# NMEA0183Breakout-3_0.net
KiCad netlist of a schematic drawn in EAGLE
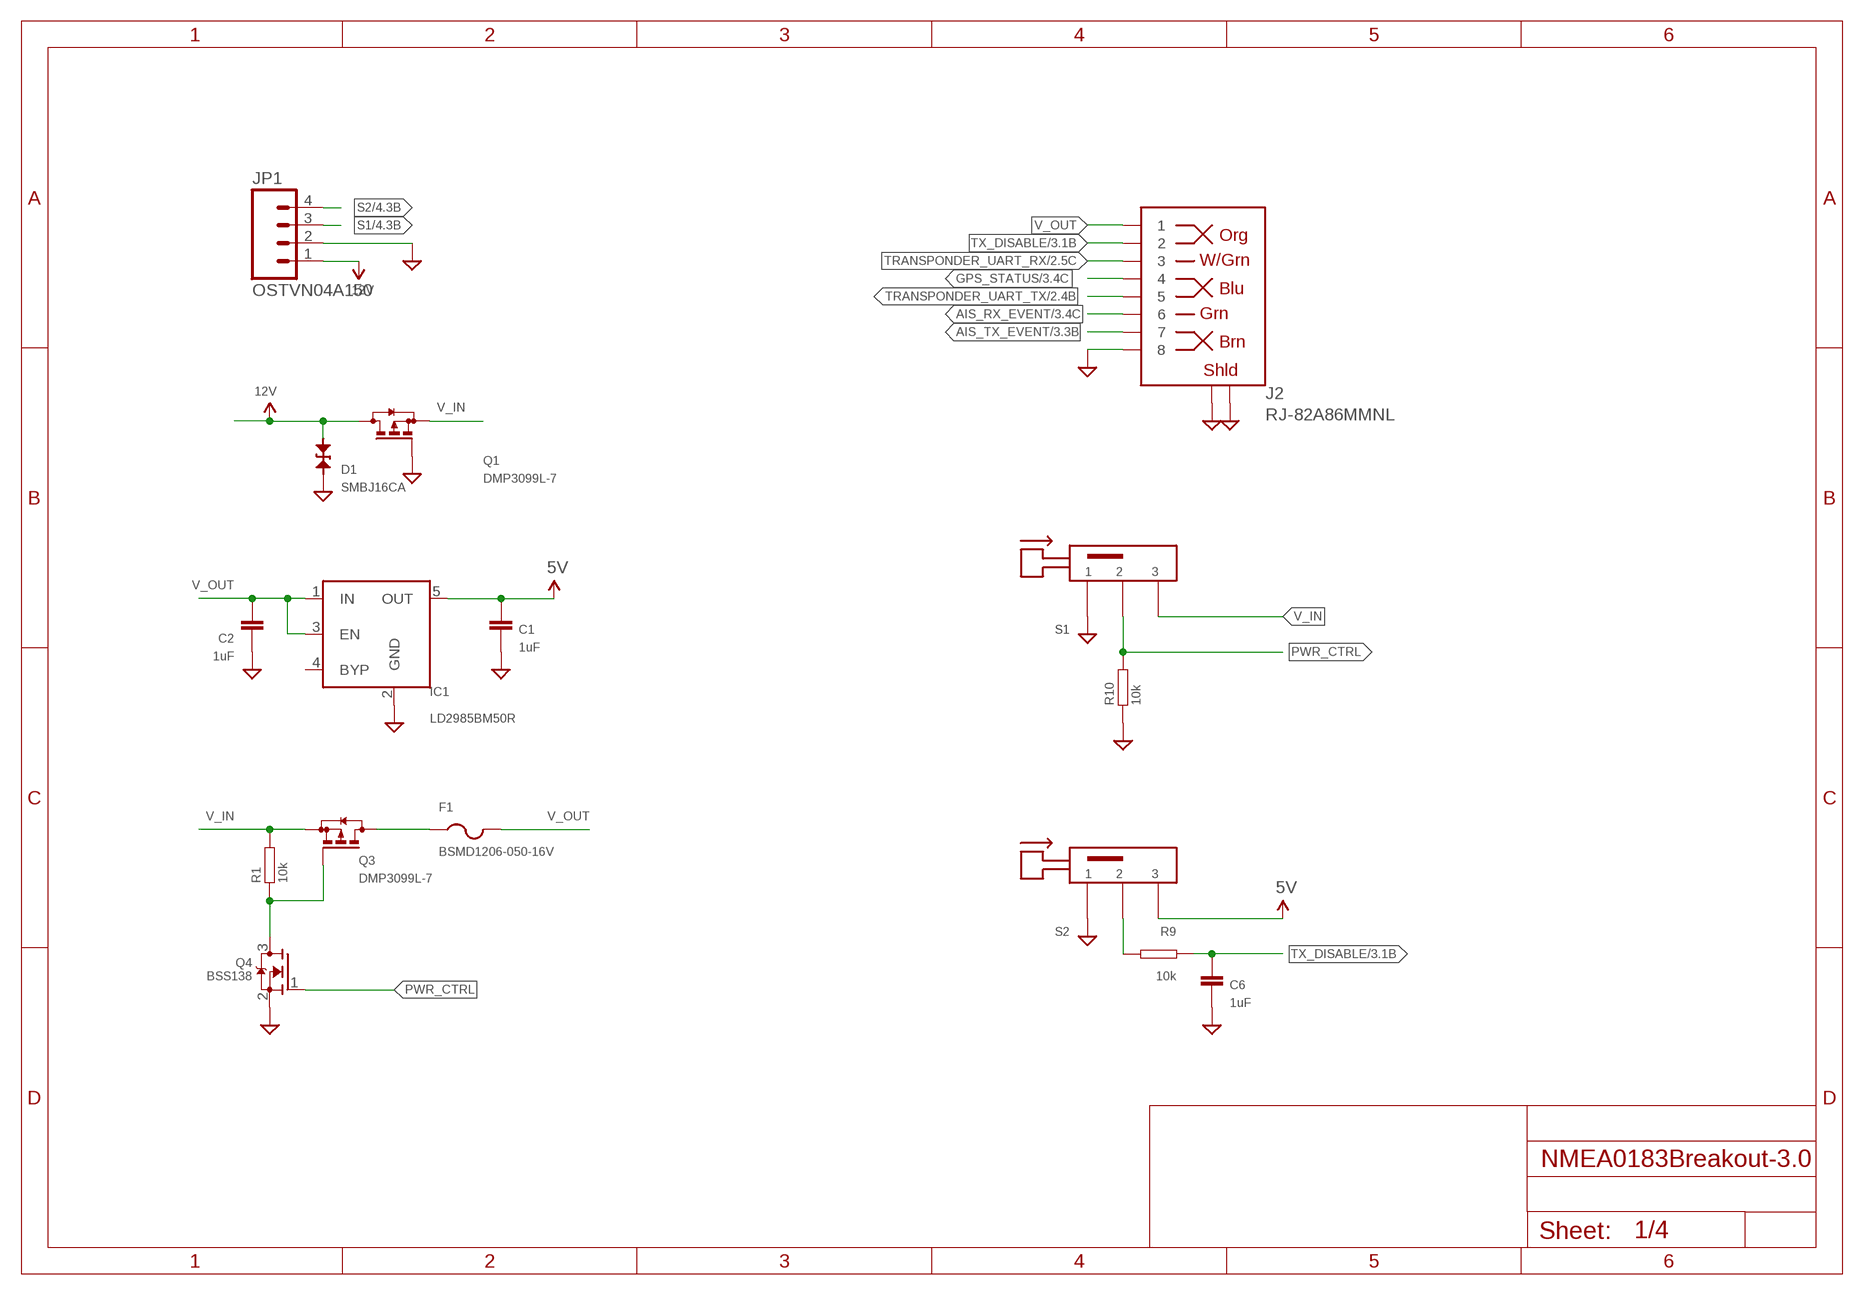
[diagram p0: schematic, sheet 1]
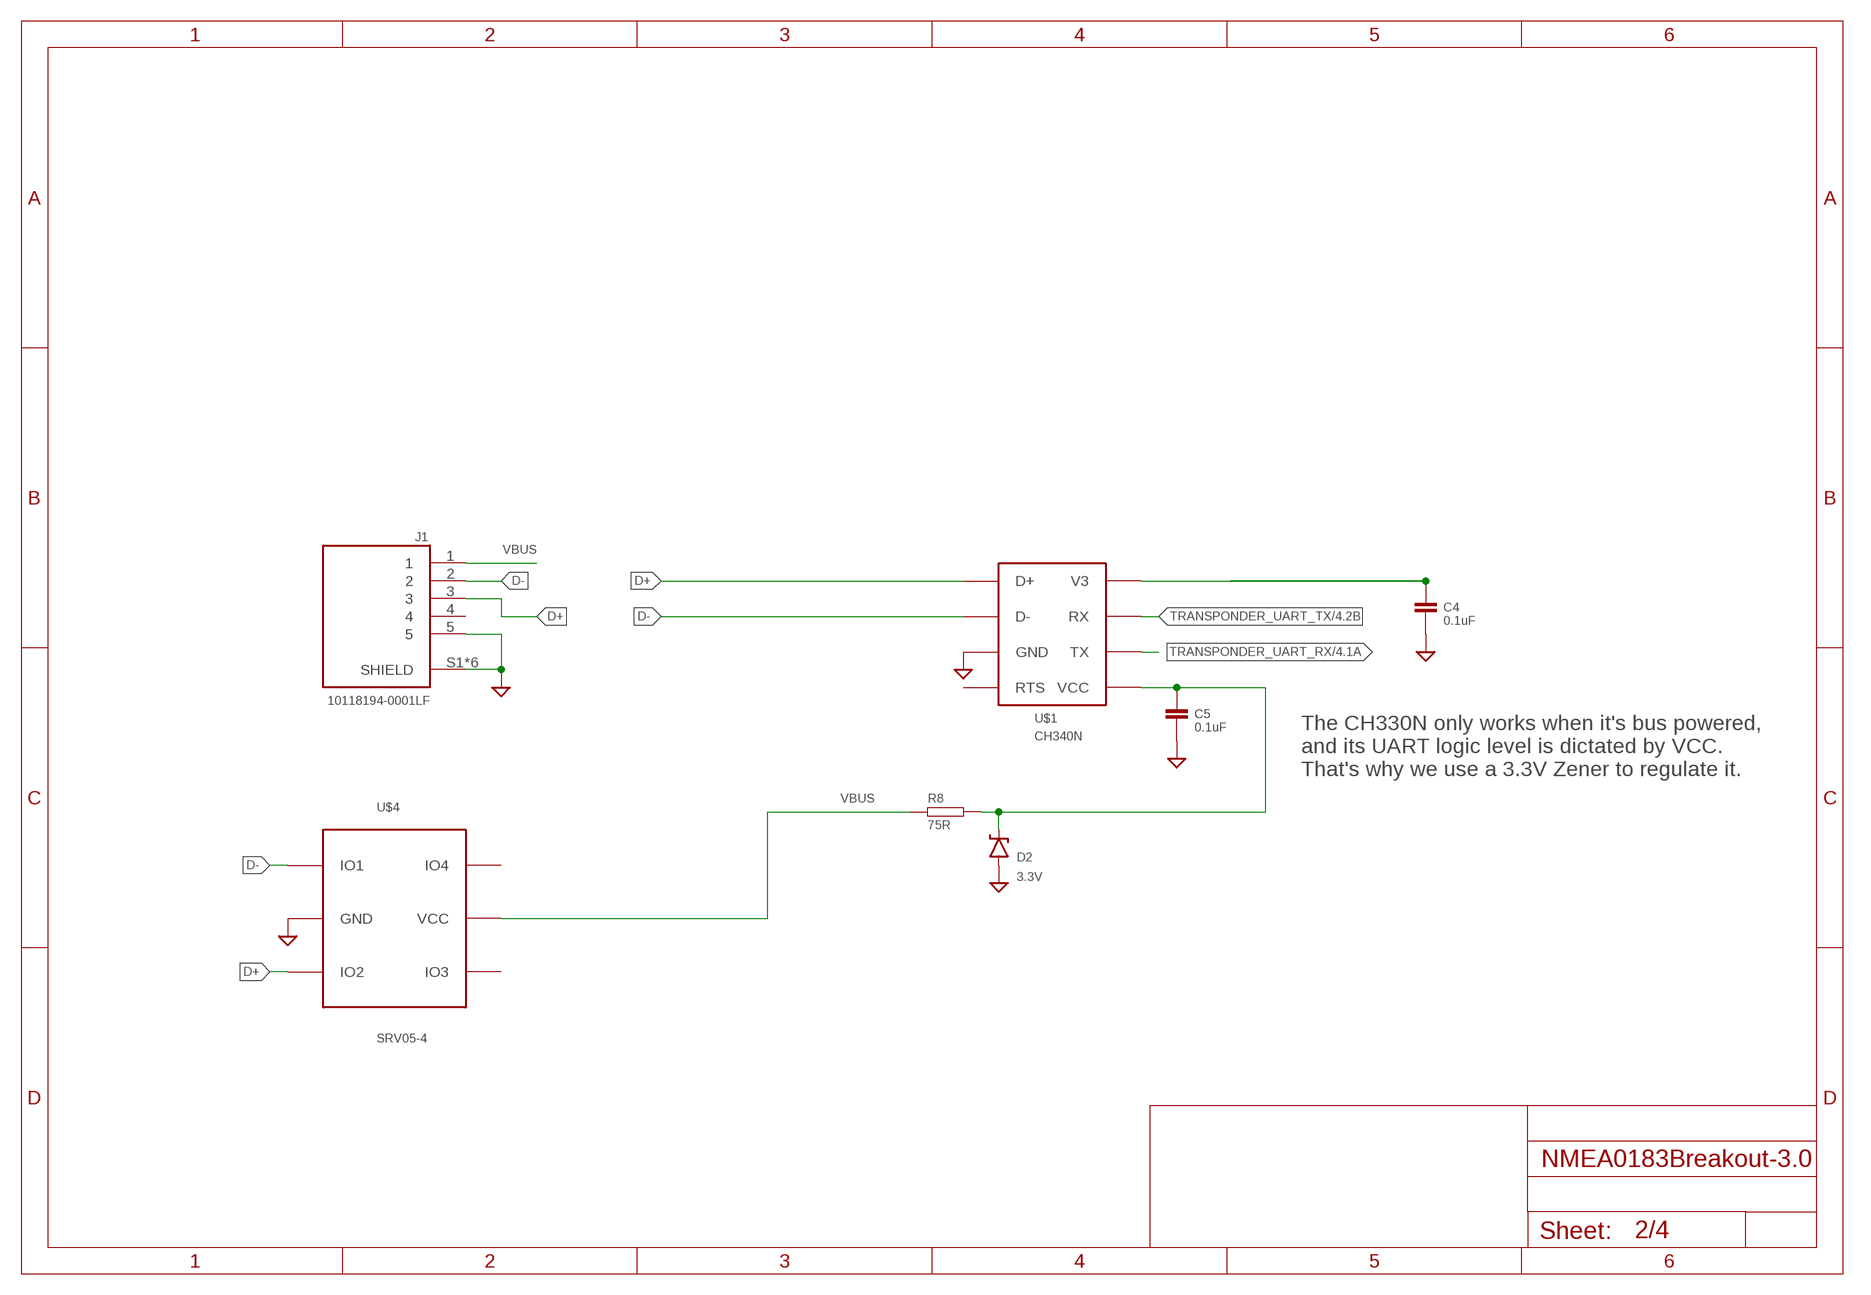
[diagram p1: schematic, sheet 2]
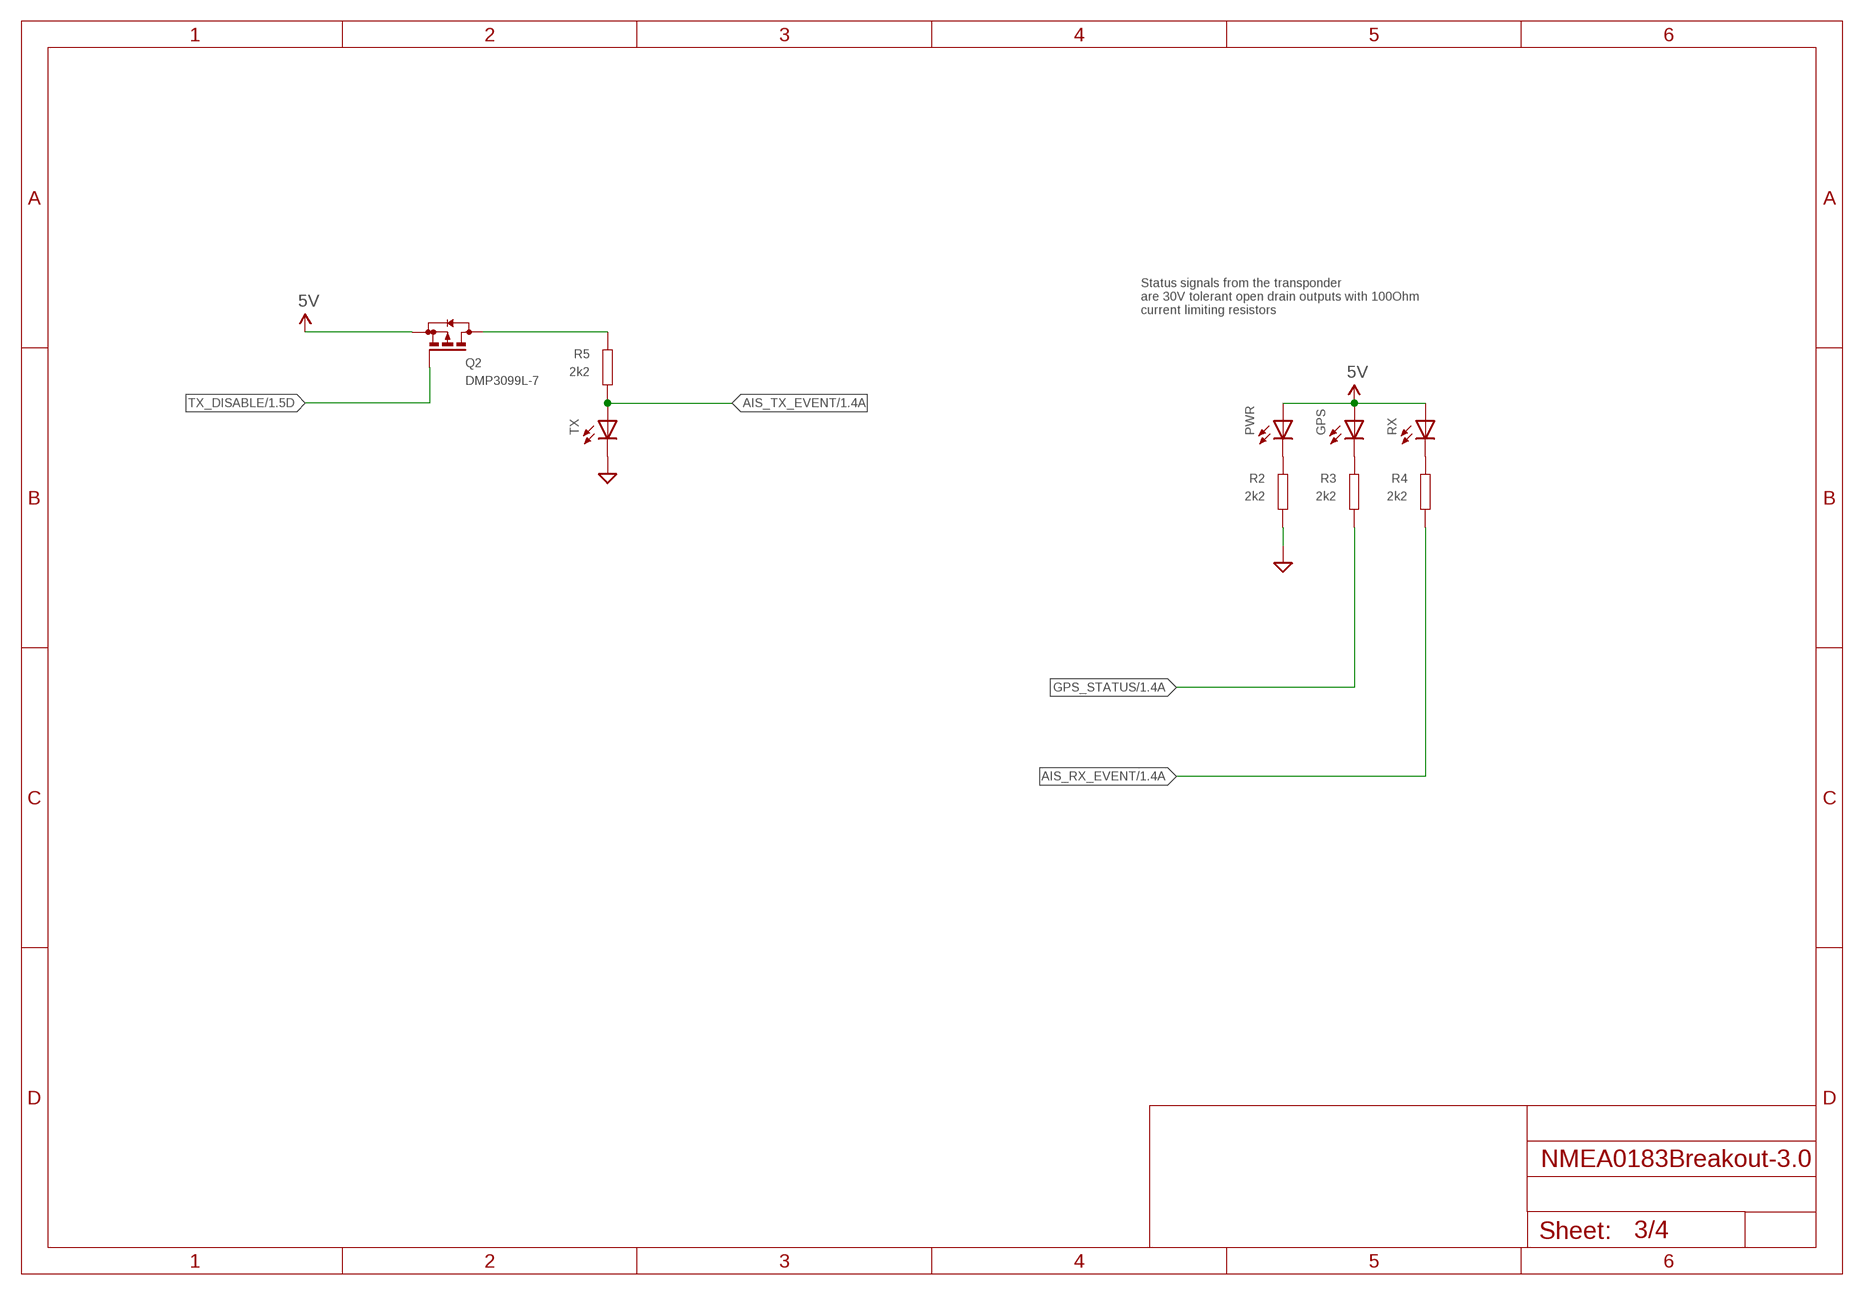
[diagram p2: schematic, sheet 3]
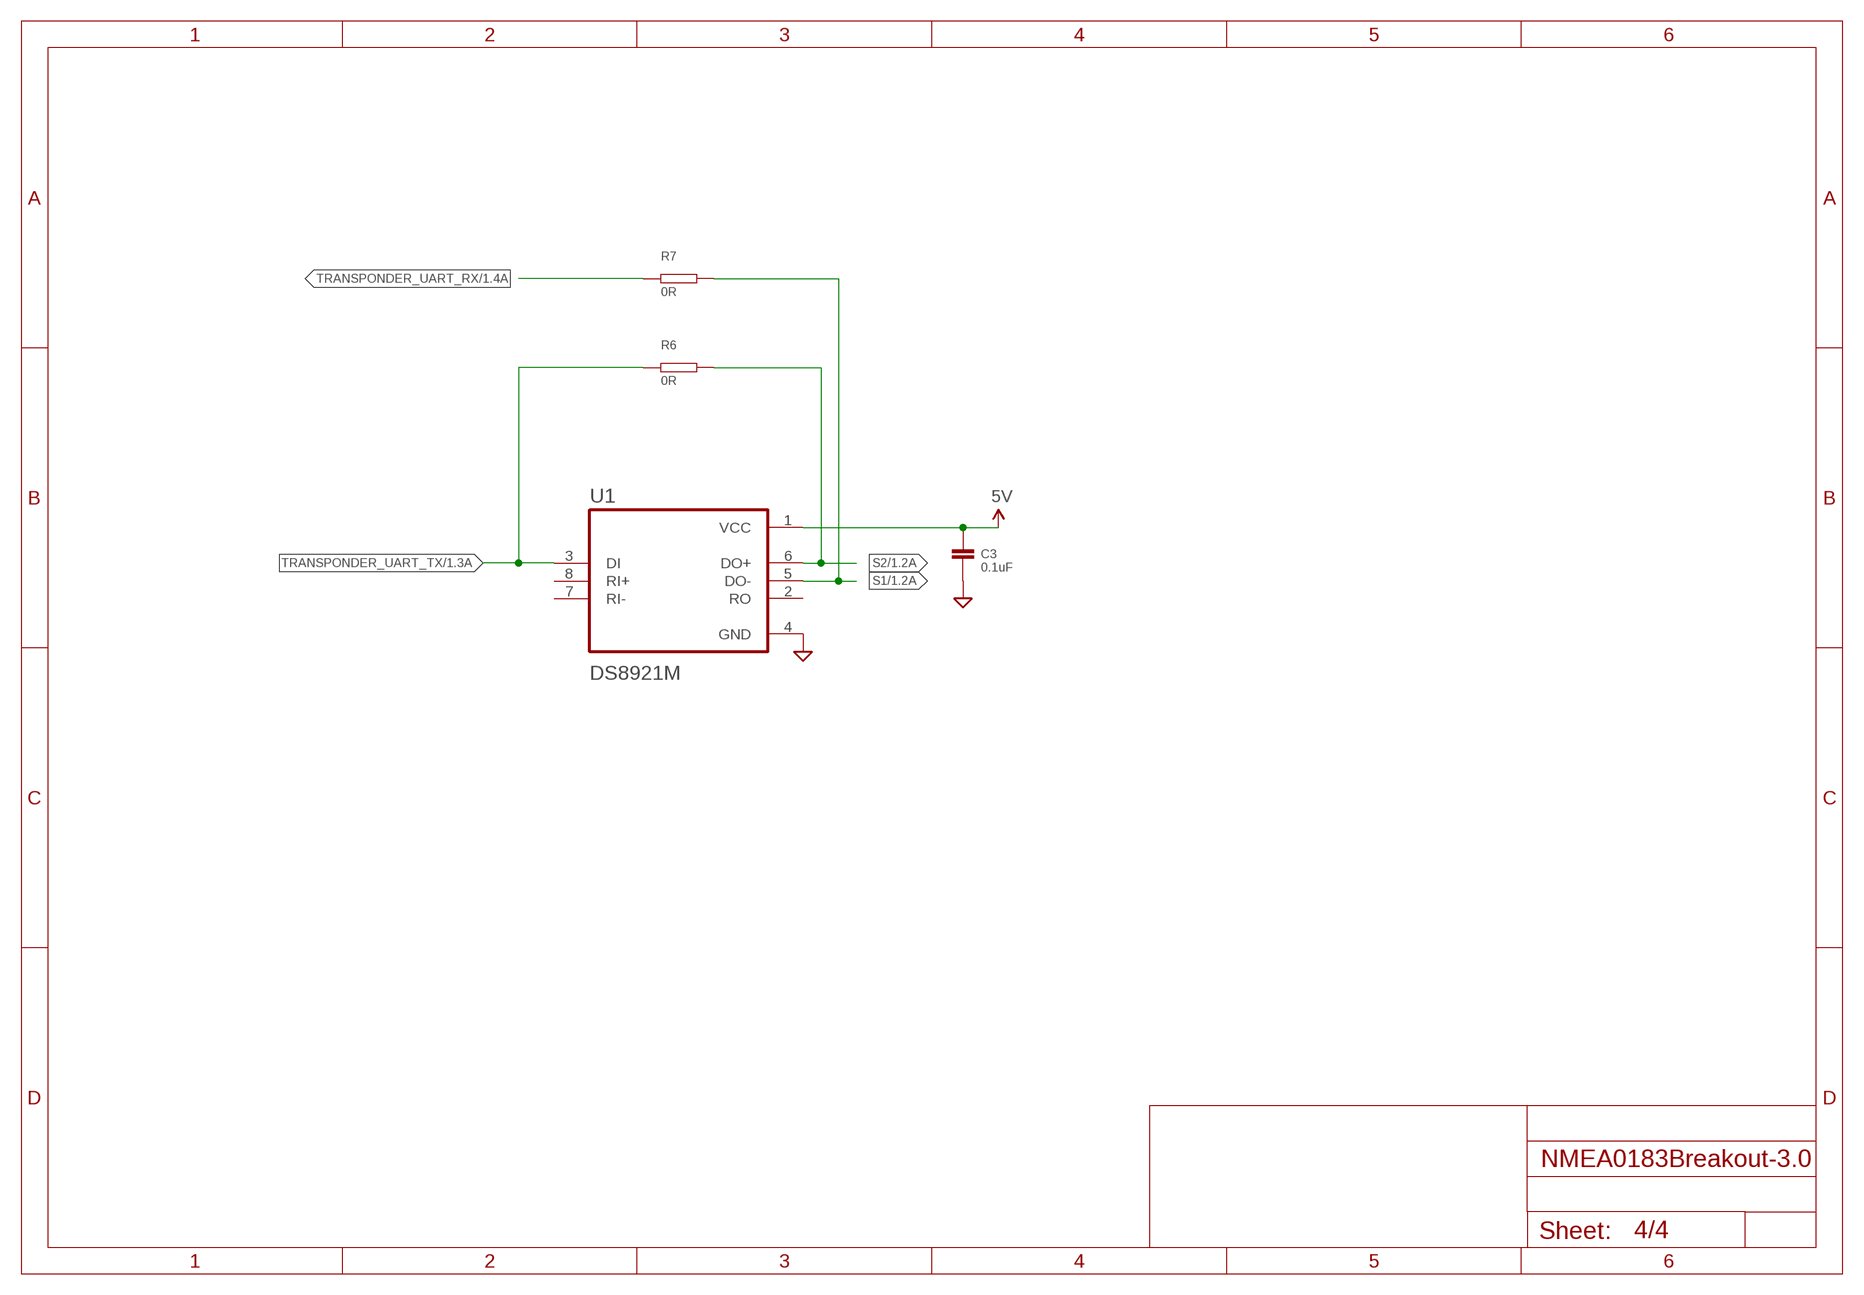
[diagram p3: schematic, sheet 4]

(export (version "E")
  (design (tool "Eeschema 10.0.6"))
  (components
    (comp (ref "C1")
      (value "1uF")
      (footprint "eagle-import:0603")
      (libsource (lib "eagle-import") (part "CAPACITOR0603"))
    )
    (comp (ref "C2")
      (value "1uF")
      (footprint "eagle-import:0603")
      (libsource (lib "eagle-import") (part "CAPACITOR0603"))
    )
    (comp (ref "C6")
      (value "1uF")
      (footprint "eagle-import:0603")
      (libsource (lib "eagle-import") (part "CAPACITOR0603"))
    )
    (comp (ref "D1")
      (value "SMBJ16CA")
      (footprint "eagle-import:SMB-BIDIR")
      (libsource (lib "eagle-import") (part "DIODE-TVS-BIDIRSMB"))
    )
    (comp (ref "F1")
      (value "BSMD1206-050-16V")
      (footprint "eagle-import:R1206")
      (libsource (lib "eagle-import") (part "PTCFUSE-1206"))
    )
    (comp (ref "IC1")
      (value "LD2985BM50R")
      (footprint "eagle-import:SOT23-5")
      (libsource (lib "eagle-import") (part "MIC5219XX"))
    )
    (comp (ref "J2")
      (value "RJ-82A86MMNL")
      (footprint "eagle-import:RJ-82A86MMNL")
      (libsource (lib "eagle-import") (part "RJ-82A86MMNL"))
    )
    (comp (ref "JP1")
      (value "OSTVN04A150")
      (footprint "eagle-import:1X04")
      (libsource (lib "eagle-import") (part "M04PTH"))
    )
    (comp (ref "Q1")
      (value "DMP3099L-7")
      (footprint "eagle-import:SOT23")
      (libsource (lib "eagle-import") (part "BSS84"))
    )
    (comp (ref "Q3")
      (value "DMP3099L-7")
      (footprint "eagle-import:SOT23")
      (libsource (lib "eagle-import") (part "BSS84"))
    )
    (comp (ref "Q4")
      (value "BSS138")
      (footprint "eagle-import:SOT23")
      (libsource (lib "eagle-import") (part "MOSFET-NREFLOW"))
    )
    (comp (ref "R1")
      (value "10k")
      (footprint "eagle-import:0603")
      (libsource (lib "eagle-import") (part "RESISTOR0603"))
    )
    (comp (ref "R9")
      (value "10k")
      (footprint "eagle-import:0603")
      (libsource (lib "eagle-import") (part "RESISTOR0603"))
    )
    (comp (ref "R10")
      (value "10k")
      (footprint "eagle-import:0603")
      (libsource (lib "eagle-import") (part "RESISTOR0603"))
    )
    (comp (ref "S1")
      (value "LC1258XXNP")
      (footprint "eagle-import:LC1258XXNP")
      (libsource (lib "eagle-import") (part "LC1258XXNP"))
    )
    (comp (ref "S2")
      (value "LC1258XXNP")
      (footprint "eagle-import:LC1258XXNP")
      (libsource (lib "eagle-import") (part "LC1258XXNP"))
    )
    (comp (ref "GPS")
      (value "LEDCHIPLED_1206")
      (footprint "eagle-import:CHIPLED_1206")
      (fields (field (name "PARTNO") "TJ-S3216CL9T5ALC2G-A5"))
      (libsource (lib "eagle-import") (part "LEDCHIPLED_1206"))
    )
    (comp (ref "PWR")
      (value "LEDCHIPLED_1206")
      (footprint "eagle-import:CHIPLED_1206")
      (fields (field (name "PARTNO") "TJ-S3216CL9T5ALC2G-A5"))
      (libsource (lib "eagle-import") (part "LEDCHIPLED_1206"))
    )
    (comp (ref "Q2")
      (value "DMP3099L-7")
      (footprint "eagle-import:SOT23")
      (libsource (lib "eagle-import") (part "BSS84"))
    )
    (comp (ref "R2")
      (value "2k2")
      (footprint "eagle-import:0603")
      (libsource (lib "eagle-import") (part "RESISTOR0603"))
    )
    (comp (ref "R3")
      (value "2k2")
      (footprint "eagle-import:0603")
      (libsource (lib "eagle-import") (part "RESISTOR0603"))
    )
    (comp (ref "R4")
      (value "2k2")
      (footprint "eagle-import:0603")
      (libsource (lib "eagle-import") (part "RESISTOR0603"))
    )
    (comp (ref "R5")
      (value "2k2")
      (footprint "eagle-import:0603")
      (libsource (lib "eagle-import") (part "RESISTOR0603"))
    )
    (comp (ref "RX")
      (value "LEDCHIPLED_1206")
      (footprint "eagle-import:CHIPLED_1206")
      (fields (field (name "PARTNO") "TJ-S3216CL9T5ALC2G-A5"))
      (libsource (lib "eagle-import") (part "LEDCHIPLED_1206"))
    )
    (comp (ref "TX")
      (value "LEDCHIPLED_1206")
      (footprint "eagle-import:CHIPLED_1206")
      (fields (field (name "PARTNO") "TJ-S3216CL9T5ALC2G-A5"))
      (libsource (lib "eagle-import") (part "LEDCHIPLED_1206"))
    )
    (comp (ref "C4")
      (value "0.1uF")
      (footprint "eagle-import:0603")
      (libsource (lib "eagle-import") (part "CAPACITOR0603"))
    )
    (comp (ref "C5")
      (value "0.1uF")
      (footprint "eagle-import:0603")
      (libsource (lib "eagle-import") (part "CAPACITOR0603"))
    )
    (comp (ref "D2")
      (value "3.3V")
      (footprint "eagle-import:SOD-323")
      (libsource (lib "eagle-import") (part "DIODE-ZENER3.3V"))
    )
    (comp (ref "J1")
      (value "10118194-0001LF")
      (footprint "eagle-import:AMPHENOL_10118194-0001LF")
      (fields (field (name "MF") "Amphenol ICC (FCI)"))
      (libsource (lib "eagle-import") (part "10118194-0001LF"))
    )
    (comp (ref "R8")
      (value "75R")
      (footprint "eagle-import:0603")
      (libsource (lib "eagle-import") (part "RESISTOR0603"))
    )
    (comp (ref "U$1")
      (value "CH340N")
      (footprint "eagle-import:SOIC-8")
      (libsource (lib "eagle-import") (part "CH330N"))
    )
    (comp (ref "U$4")
      (value "SRV05-4")
      (footprint "eagle-import:SOT23-6")
      (libsource (lib "eagle-import") (part "SRV05-4"))
    )
    (comp (ref "C3")
      (value "0.1uF")
      (footprint "eagle-import:0603")
      (libsource (lib "eagle-import") (part "CAPACITOR0603"))
    )
    (comp (ref "R6")
      (value "0R")
      (footprint "eagle-import:0603")
      (libsource (lib "eagle-import") (part "RESISTOR0603"))
    )
    (comp (ref "R7")
      (value "0R")
      (footprint "eagle-import:0603")
      (libsource (lib "eagle-import") (part "RESISTOR0603"))
    )
    (comp (ref "U1")
      (value "DS8921M")
      (footprint "eagle-import:SOIC127P599X175-8N")
      (fields (field (name "MF") "Texas Instruments") (field (name "MP") "DS8921M/NOPB"))
      (libsource (lib "eagle-import") (part "DS8921M"))
    )
  )
  (nets
    (net (code "1") (name "5V") (class "Default")
      (node (ref "C1") (pin "P$1") (pinfunction "1_P$1") (pintype "passive"))
      (node (ref "C3") (pin "P$1") (pinfunction "1_P$1") (pintype "passive"))
      (node (ref "GPS") (pin "A") (pinfunction "A_A") (pintype "passive"))
      (node (ref "IC1") (pin "5") (pinfunction "OUT_5") (pintype "output"))
      (node (ref "PWR") (pin "A") (pinfunction "A_A") (pintype "passive"))
      (node (ref "Q2") (pin "2") (pinfunction "S_2") (pintype "passive"))
      (node (ref "RX") (pin "A") (pinfunction "A_A") (pintype "passive"))
      (node (ref "S2") (pin "P$3") (pinfunction "3_P$3") (pintype "bidirectional"))
      (node (ref "U1") (pin "1") (pinfunction "VCC_1") (pintype "power_in"))
    )
    (net (code "2") (name "12V") (class "Default")
      (node (ref "D1") (pin "A") (pinfunction "P$1_A") (pintype "bidirectional"))
      (node (ref "JP1") (pin "1") (pinfunction "1_1") (pintype "passive"))
      (node (ref "Q1") (pin "3") (pinfunction "D_3") (pintype "passive"))
    )
    (net (code "3") (name "AIS_RX_EVENT") (class "Default")
      (node (ref "J2") (pin "P$6") (pinfunction "6_P$6") (pintype "bidirectional"))
      (node (ref "R4") (pin "P$2") (pinfunction "P$2_P$2") (pintype "passive"))
    )
    (net (code "4") (name "AIS_TX_EVENT") (class "Default")
      (node (ref "J2") (pin "P$7") (pinfunction "7_P$7") (pintype "bidirectional"))
      (node (ref "R5") (pin "P$2") (pinfunction "P$2_P$2") (pintype "passive"))
      (node (ref "TX") (pin "A") (pinfunction "A_A") (pintype "passive"))
    )
    (net (code "5") (name "D+") (class "Default")
      (node (ref "J1") (pin "3") (pinfunction "3_3") (pintype "passive"))
      (node (ref "U$1") (pin "1") (pinfunction "D+_1") (pintype "bidirectional"))
      (node (ref "U$4") (pin "3") (pinfunction "IO2_3") (pintype "bidirectional"))
    )
    (net (code "6") (name "D-") (class "Default")
      (node (ref "J1") (pin "2") (pinfunction "2_2") (pintype "passive"))
      (node (ref "U$1") (pin "2") (pinfunction "D-_2") (pintype "bidirectional"))
      (node (ref "U$4") (pin "1") (pinfunction "IO1_1") (pintype "bidirectional"))
    )
    (net (code "7") (name "GND") (class "Default")
      (node (ref "C1") (pin "P$2") (pinfunction "2_P$2") (pintype "passive"))
      (node (ref "C2") (pin "P$2") (pinfunction "2_P$2") (pintype "passive"))
      (node (ref "C3") (pin "P$2") (pinfunction "2_P$2") (pintype "passive"))
      (node (ref "C4") (pin "P$2") (pinfunction "2_P$2") (pintype "passive"))
      (node (ref "C5") (pin "P$2") (pinfunction "2_P$2") (pintype "passive"))
      (node (ref "C6") (pin "P$2") (pinfunction "2_P$2") (pintype "passive"))
      (node (ref "D1") (pin "C") (pinfunction "P$2_C") (pintype "bidirectional"))
      (node (ref "D2") (pin "A") (pinfunction "A_A") (pintype "passive"))
      (node (ref "IC1") (pin "2") (pinfunction "GND_2") (pintype "power_in"))
      (node (ref "J1") (pin "5") (pinfunction "5_5") (pintype "passive"))
      (node (ref "J1") (pin "S1") (pinfunction "SHIELD_S1") (pintype "passive"))
      (node (ref "J1") (pin "S2") (pinfunction "SHIELD_S2") (pintype "passive"))
      (node (ref "J1") (pin "S3") (pinfunction "SHIELD_S3") (pintype "passive"))
      (node (ref "J1") (pin "S4") (pinfunction "SHIELD_S4") (pintype "passive"))
      (node (ref "J1") (pin "S5") (pinfunction "SHIELD_S5") (pintype "passive"))
      (node (ref "J1") (pin "S6") (pinfunction "SHIELD_S6") (pintype "passive"))
      (node (ref "J2") (pin "P$10") (pinfunction "SHLD_P$10") (pintype "bidirectional"))
      (node (ref "J2") (pin "P$11") (pinfunction "SHLD_P$11") (pintype "bidirectional"))
      (node (ref "J2") (pin "P$12") (pinfunction "SHLD_P$12") (pintype "bidirectional"))
      (node (ref "J2") (pin "P$8") (pinfunction "8_P$8") (pintype "bidirectional"))
      (node (ref "J2") (pin "P$9") (pinfunction "SHLD_P$9") (pintype "bidirectional"))
      (node (ref "JP1") (pin "2") (pinfunction "2_2") (pintype "passive"))
      (node (ref "Q1") (pin "1") (pinfunction "G_1") (pintype "passive"))
      (node (ref "Q4") (pin "2") (pinfunction "S_2") (pintype "bidirectional"))
      (node (ref "R10") (pin "P$1") (pinfunction "P$1_P$1") (pintype "passive"))
      (node (ref "R2") (pin "P$2") (pinfunction "P$2_P$2") (pintype "passive"))
      (node (ref "S1") (pin "P$1") (pinfunction "1_P$1") (pintype "bidirectional"))
      (node (ref "S2") (pin "P$1") (pinfunction "1_P$1") (pintype "bidirectional"))
      (node (ref "TX") (pin "C") (pinfunction "C_C") (pintype "passive"))
      (node (ref "U$1") (pin "3") (pinfunction "GND_3") (pintype "bidirectional"))
      (node (ref "U$4") (pin "2") (pinfunction "GND_2") (pintype "bidirectional"))
      (node (ref "U1") (pin "4") (pinfunction "GND_4") (pintype "power_in"))
    )
    (net (code "8") (name "GPS_STATUS") (class "Default")
      (node (ref "J2") (pin "P$4") (pinfunction "4_P$4") (pintype "bidirectional"))
      (node (ref "R3") (pin "P$2") (pinfunction "P$2_P$2") (pintype "passive"))
    )
    (net (code "9") (name "Net-(C4-1)") (class "Default")
      (node (ref "C4") (pin "P$1") (pinfunction "1_P$1") (pintype "passive"))
      (node (ref "U$1") (pin "8") (pinfunction "V3_8") (pintype "bidirectional"))
    )
    (net (code "10") (name "Net-(C5-1)") (class "Default")
      (node (ref "C5") (pin "P$1") (pinfunction "1_P$1") (pintype "passive"))
      (node (ref "D2") (pin "C") (pinfunction "C_C") (pintype "passive"))
      (node (ref "R8") (pin "P$2") (pinfunction "P$2_P$2") (pintype "passive"))
      (node (ref "U$1") (pin "5") (pinfunction "VCC_5") (pintype "bidirectional"))
    )
    (net (code "11") (name "Net-(GPS-PadC)") (class "Default")
      (node (ref "GPS") (pin "C") (pinfunction "C_C") (pintype "passive"))
      (node (ref "R3") (pin "P$1") (pinfunction "P$1_P$1") (pintype "passive"))
    )
    (net (code "12") (name "Net-(PWR-PadC)") (class "Default")
      (node (ref "PWR") (pin "C") (pinfunction "C_C") (pintype "passive"))
      (node (ref "R2") (pin "P$1") (pinfunction "P$1_P$1") (pintype "passive"))
    )
    (net (code "13") (name "Net-(Q2-D)") (class "Default")
      (node (ref "Q2") (pin "3") (pinfunction "D_3") (pintype "passive"))
      (node (ref "R5") (pin "P$1") (pinfunction "P$1_P$1") (pintype "passive"))
    )
    (net (code "14") (name "Net-(Q3-D)") (class "Default")
      (node (ref "F1") (pin "1") (pinfunction "1_1") (pintype "passive"))
      (node (ref "Q3") (pin "3") (pinfunction "D_3") (pintype "passive"))
    )
    (net (code "15") (name "Net-(Q3-G)") (class "Default")
      (node (ref "Q3") (pin "1") (pinfunction "G_1") (pintype "passive"))
      (node (ref "Q4") (pin "3") (pinfunction "D_3") (pintype "bidirectional"))
      (node (ref "R1") (pin "P$1") (pinfunction "P$1_P$1") (pintype "passive"))
    )
    (net (code "16") (name "Net-(R4-PadP$1)") (class "Default")
      (node (ref "R4") (pin "P$1") (pinfunction "P$1_P$1") (pintype "passive"))
      (node (ref "RX") (pin "C") (pinfunction "C_C") (pintype "passive"))
    )
    (net (code "17") (name "Net-(S2-2)") (class "Default")
      (node (ref "R9") (pin "P$2") (pinfunction "P$2_P$2") (pintype "passive"))
      (node (ref "S2") (pin "P$2") (pinfunction "2_P$2") (pintype "bidirectional"))
    )
    (net (code "18") (name "PWR_CTRL") (class "Default")
      (node (ref "Q4") (pin "1") (pinfunction "G_1") (pintype "bidirectional"))
      (node (ref "R10") (pin "P$2") (pinfunction "P$2_P$2") (pintype "passive"))
      (node (ref "S1") (pin "P$2") (pinfunction "2_P$2") (pintype "bidirectional"))
    )
    (net (code "19") (name "S1") (class "Default")
      (node (ref "JP1") (pin "3") (pinfunction "3_3") (pintype "passive"))
      (node (ref "R7") (pin "P$2") (pinfunction "P$2_P$2") (pintype "passive"))
      (node (ref "U1") (pin "5") (pinfunction "DO-_5") (pintype "output"))
    )
    (net (code "20") (name "S2") (class "Default")
      (node (ref "JP1") (pin "4") (pinfunction "4_4") (pintype "passive"))
      (node (ref "R6") (pin "P$2") (pinfunction "P$2_P$2") (pintype "passive"))
      (node (ref "U1") (pin "6") (pinfunction "DO+_6") (pintype "output"))
    )
    (net (code "21") (name "TRANSPONDER_UART_RX") (class "Default")
      (node (ref "J2") (pin "P$3") (pinfunction "3_P$3") (pintype "bidirectional"))
      (node (ref "R7") (pin "P$1") (pinfunction "P$1_P$1") (pintype "passive"))
      (node (ref "U$1") (pin "6") (pinfunction "TX_6") (pintype "bidirectional"))
    )
    (net (code "22") (name "TRANSPONDER_UART_TX") (class "Default")
      (node (ref "J2") (pin "P$5") (pinfunction "5_P$5") (pintype "bidirectional"))
      (node (ref "R6") (pin "P$1") (pinfunction "P$1_P$1") (pintype "passive"))
      (node (ref "U$1") (pin "7") (pinfunction "RX_7") (pintype "bidirectional"))
      (node (ref "U1") (pin "3") (pinfunction "DI_3") (pintype "input"))
    )
    (net (code "23") (name "TX_DISABLE") (class "Default")
      (node (ref "C6") (pin "P$1") (pinfunction "1_P$1") (pintype "passive"))
      (node (ref "J2") (pin "P$2") (pinfunction "2_P$2") (pintype "bidirectional"))
      (node (ref "Q2") (pin "1") (pinfunction "G_1") (pintype "passive"))
      (node (ref "R9") (pin "P$1") (pinfunction "P$1_P$1") (pintype "passive"))
    )
    (net (code "24") (name "VBUS") (class "Default")
      (node (ref "J1") (pin "1") (pinfunction "1_1") (pintype "passive"))
      (node (ref "R8") (pin "P$1") (pinfunction "P$1_P$1") (pintype "passive"))
      (node (ref "U$4") (pin "5") (pinfunction "VCC_5") (pintype "bidirectional"))
    )
    (net (code "25") (name "V_IN") (class "Default")
      (node (ref "Q1") (pin "2") (pinfunction "S_2") (pintype "passive"))
      (node (ref "Q3") (pin "2") (pinfunction "S_2") (pintype "passive"))
      (node (ref "R1") (pin "P$2") (pinfunction "P$2_P$2") (pintype "passive"))
      (node (ref "S1") (pin "P$3") (pinfunction "3_P$3") (pintype "bidirectional"))
    )
    (net (code "26") (name "V_OUT") (class "Default")
      (node (ref "C2") (pin "P$1") (pinfunction "1_P$1") (pintype "passive"))
      (node (ref "F1") (pin "2") (pinfunction "2_2") (pintype "passive"))
      (node (ref "IC1") (pin "1") (pinfunction "IN_1") (pintype "input"))
      (node (ref "IC1") (pin "3") (pinfunction "EN_3") (pintype "input"))
      (node (ref "J2") (pin "P$1") (pinfunction "1_P$1") (pintype "bidirectional"))
    )
    (net (code "27") (name "unconnected-(IC1-BYP-Pad4)") (class "Default")
      (node (ref "IC1") (pin "4") (pinfunction "BYP_4") (pintype "passive"))
    )
    (net (code "28") (name "unconnected-(J1-Pad4)") (class "Default")
      (node (ref "J1") (pin "4") (pinfunction "4_4") (pintype "passive"))
    )
    (net (code "29") (name "unconnected-(U$1-RTS-Pad4)") (class "Default")
      (node (ref "U$1") (pin "4") (pinfunction "RTS_4") (pintype "bidirectional"))
    )
    (net (code "30") (name "unconnected-(U$4-IO3-Pad4)") (class "Default")
      (node (ref "U$4") (pin "4") (pinfunction "IO3_4") (pintype "bidirectional"))
    )
    (net (code "31") (name "unconnected-(U$4-IO4-Pad6)") (class "Default")
      (node (ref "U$4") (pin "6") (pinfunction "IO4_6") (pintype "bidirectional"))
    )
    (net (code "32") (name "unconnected-(U1-RI+-Pad8)") (class "Default")
      (node (ref "U1") (pin "8") (pinfunction "RI+_8") (pintype "input"))
    )
    (net (code "33") (name "unconnected-(U1-RI--Pad7)") (class "Default")
      (node (ref "U1") (pin "7") (pinfunction "RI-_7") (pintype "input"))
    )
    (net (code "34") (name "unconnected-(U1-RO-Pad2)") (class "Default")
      (node (ref "U1") (pin "2") (pinfunction "RO_2") (pintype "output"))
    )
  )
)
